# MRCS-ODX4_v17.net
KiCad netlist of a schematic drawn in EAGLE
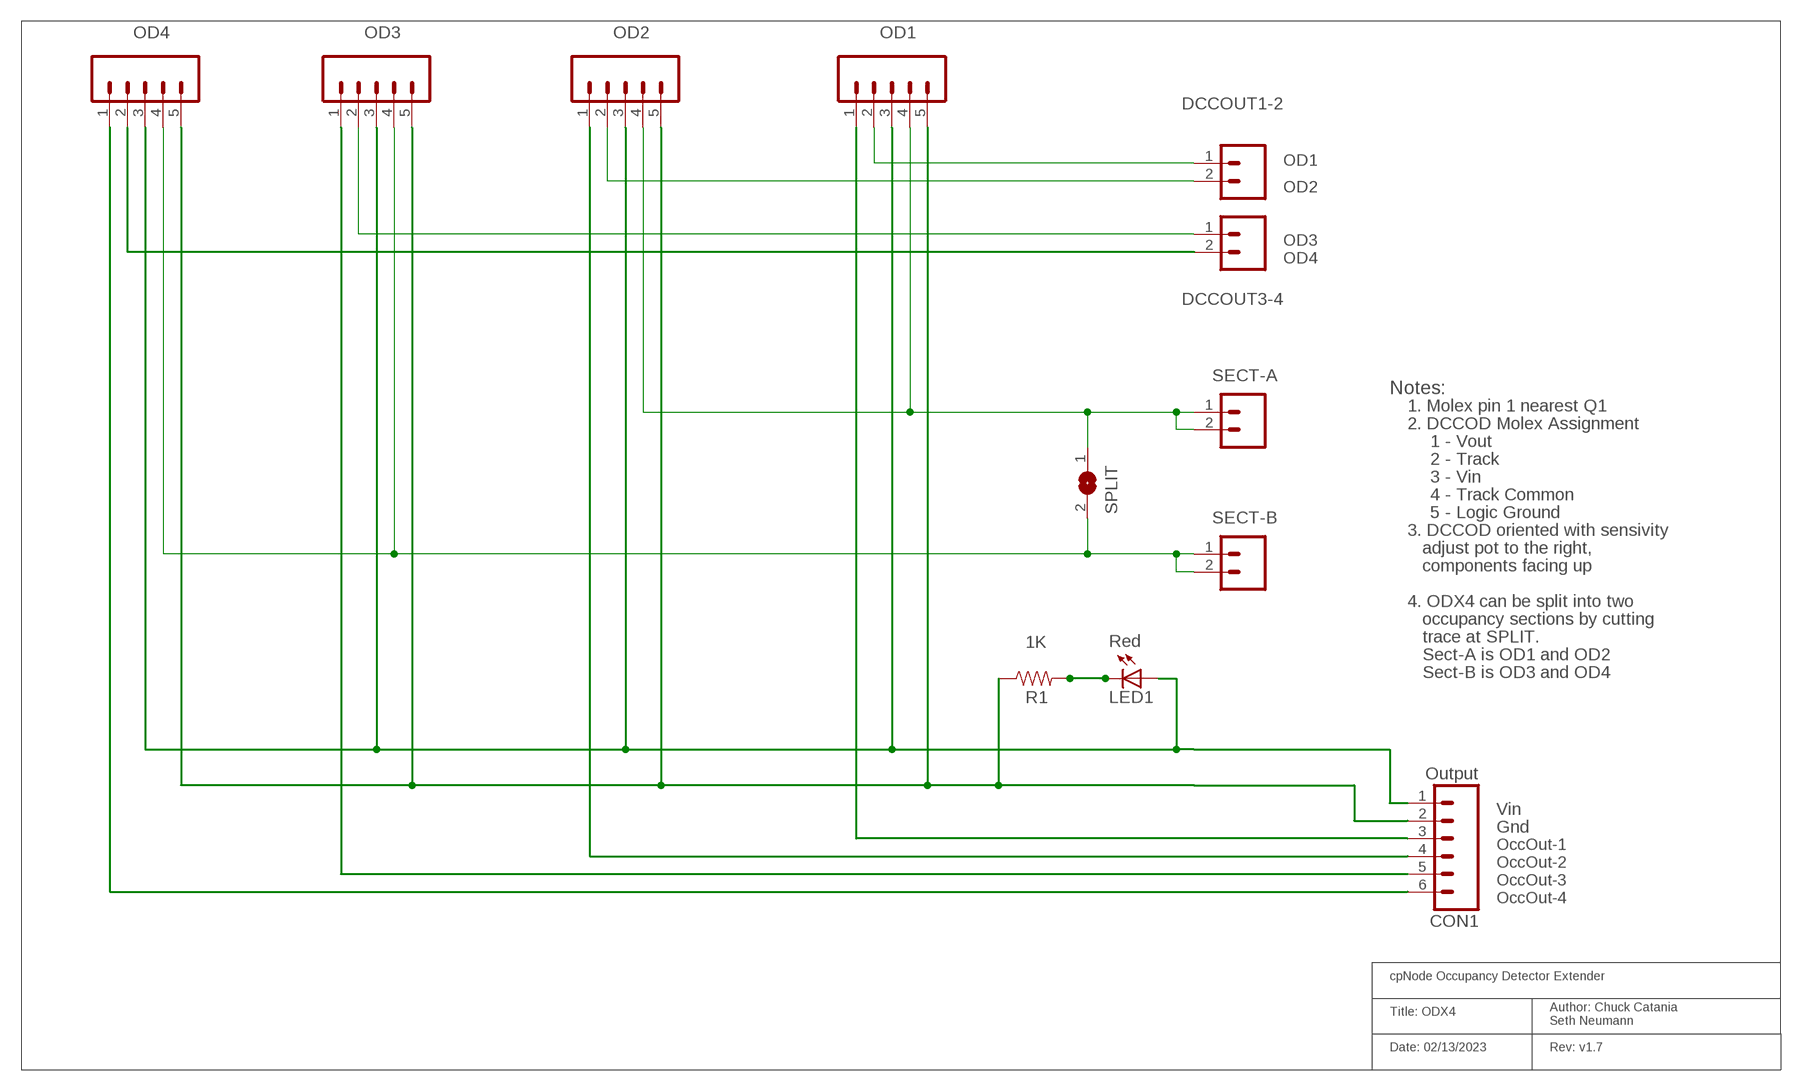
[diagram p0: schematic, sheet 1]

(export (version "E")
  (design (tool "Eeschema 10.0.6"))
  (components
    (comp (ref "CON1")
      (value "Output")
      (footprint "eagle-import:MOLEX-1X6_LOCK")
      (libsource (lib "eagle-import") (part "CONNECTOR-M06POLAR_LOCK"))
    )
    (comp (ref "DCCOUT1-2")
      (value "CONNECTOR-M025MM-LOCK")
      (footprint "eagle-import:SCREWTERMINAL-5MM-2")
      (libsource (lib "eagle-import") (part "CONNECTOR-M025MM-LOCK"))
    )
    (comp (ref "DCCOUT3-4")
      (value "CONNECTOR-M025MM-LOCK")
      (footprint "eagle-import:SCREWTERMINAL-5MM-2")
      (libsource (lib "eagle-import") (part "CONNECTOR-M025MM-LOCK"))
    )
    (comp (ref "LED1")
      (value "Red")
      (footprint "eagle-import:LED3MM")
      (libsource (lib "eagle-import") (part "LEDLED3MM"))
    )
    (comp (ref "OD1")
      (value "M05PTH_LONGPADS")
      (footprint "eagle-import:1X05_LONGPADS")
      (libsource (lib "eagle-import") (part "M05PTH_LONGPADS"))
    )
    (comp (ref "OD2")
      (value "M05PTH_LONGPADS")
      (footprint "eagle-import:1X05_LONGPADS")
      (libsource (lib "eagle-import") (part "M05PTH_LONGPADS"))
    )
    (comp (ref "OD3")
      (value "M05PTH_LONGPADS")
      (footprint "eagle-import:1X05_LONGPADS")
      (libsource (lib "eagle-import") (part "M05PTH_LONGPADS"))
    )
    (comp (ref "OD4")
      (value "M05PTH_LONGPADS")
      (footprint "eagle-import:1X05_LONGPADS")
      (libsource (lib "eagle-import") (part "M05PTH_LONGPADS"))
    )
    (comp (ref "R1")
      (value "1K")
      (footprint "eagle-import:AXIAL-0.4-RES")
      (libsource (lib "eagle-import") (part "RPTH04"))
    )
    (comp (ref "SECT-A")
      (value "M025MM")
      (footprint "eagle-import:SCREWTERMINAL-5MM-2")
      (libsource (lib "eagle-import") (part "M025MM"))
    )
    (comp (ref "SECT-B")
      (value "M025MM")
      (footprint "eagle-import:SCREWTERMINAL-5MM-2")
      (libsource (lib "eagle-import") (part "M025MM"))
    )
    (comp (ref "SPLIT")
      (value "SJW")
      (footprint "eagle-import:SJW")
      (libsource (lib "eagle-import") (part "SJW"))
    )
  )
  (nets
    (net (code "1") (name "Net-(CON1-Pad1)") (class "Default")
      (node (ref "CON1") (pin "1") (pinfunction "1_1") (pintype "passive"))
      (node (ref "LED1") (pin "A") (pinfunction "A_A") (pintype "passive"))
      (node (ref "OD1") (pin "3") (pinfunction "3_3") (pintype "passive"))
      (node (ref "OD2") (pin "3") (pinfunction "3_3") (pintype "passive"))
      (node (ref "OD3") (pin "3") (pinfunction "3_3") (pintype "passive"))
      (node (ref "OD4") (pin "3") (pinfunction "3_3") (pintype "passive"))
    )
    (net (code "2") (name "Net-(CON1-Pad3)") (class "Default")
      (node (ref "CON1") (pin "3") (pinfunction "3_3") (pintype "passive"))
      (node (ref "OD1") (pin "1") (pinfunction "1_1") (pintype "passive"))
    )
    (net (code "3") (name "Net-(CON1-Pad4)") (class "Default")
      (node (ref "CON1") (pin "4") (pinfunction "4_4") (pintype "passive"))
      (node (ref "OD2") (pin "1") (pinfunction "1_1") (pintype "passive"))
    )
    (net (code "4") (name "Net-(CON1-Pad5)") (class "Default")
      (node (ref "CON1") (pin "5") (pinfunction "5_5") (pintype "passive"))
      (node (ref "OD3") (pin "1") (pinfunction "1_1") (pintype "passive"))
    )
    (net (code "5") (name "Net-(CON1-Pad6)") (class "Default")
      (node (ref "CON1") (pin "6") (pinfunction "6_6") (pintype "passive"))
      (node (ref "OD4") (pin "1") (pinfunction "1_1") (pintype "passive"))
    )
    (net (code "6") (name "Net-(DCCOUT1-2-A)") (class "Default")
      (node (ref "DCCOUT1-2") (pin "1") (pinfunction "A_1") (pintype "passive"))
      (node (ref "OD1") (pin "2") (pinfunction "2_2") (pintype "passive"))
    )
    (net (code "7") (name "Net-(DCCOUT1-2-B)") (class "Default")
      (node (ref "DCCOUT1-2") (pin "2") (pinfunction "B_2") (pintype "passive"))
      (node (ref "OD2") (pin "2") (pinfunction "2_2") (pintype "passive"))
    )
    (net (code "8") (name "Net-(DCCOUT3-4-A)") (class "Default")
      (node (ref "DCCOUT3-4") (pin "1") (pinfunction "A_1") (pintype "passive"))
      (node (ref "OD3") (pin "2") (pinfunction "2_2") (pintype "passive"))
    )
    (net (code "9") (name "Net-(DCCOUT3-4-B)") (class "Default")
      (node (ref "DCCOUT3-4") (pin "2") (pinfunction "B_2") (pintype "passive"))
      (node (ref "OD4") (pin "2") (pinfunction "2_2") (pintype "passive"))
    )
    (net (code "10") (name "Net-(LED1-C)") (class "Default")
      (node (ref "LED1") (pin "K") (pinfunction "C_K") (pintype "passive"))
      (node (ref "R1") (pin "P$2") (pinfunction "2_P$2") (pintype "passive"))
    )
    (net (code "11") (name "Net-(OD1-Pad4)") (class "Default")
      (node (ref "OD1") (pin "4") (pinfunction "4_4") (pintype "passive"))
      (node (ref "OD2") (pin "4") (pinfunction "4_4") (pintype "passive"))
      (node (ref "SECT-A") (pin "1") (pinfunction "1_1") (pintype "passive"))
      (node (ref "SECT-A") (pin "2") (pinfunction "2_2") (pintype "passive"))
      (node (ref "SPLIT") (pin "1") (pinfunction "1_1") (pintype "passive"))
    )
    (net (code "12") (name "Net-(OD3-Pad4)") (class "Default")
      (node (ref "OD3") (pin "4") (pinfunction "4_4") (pintype "passive"))
      (node (ref "OD4") (pin "4") (pinfunction "4_4") (pintype "passive"))
      (node (ref "SECT-B") (pin "1") (pinfunction "1_1") (pintype "passive"))
      (node (ref "SECT-B") (pin "2") (pinfunction "2_2") (pintype "passive"))
      (node (ref "SPLIT") (pin "2") (pinfunction "2_2") (pintype "passive"))
    )
    (net (code "13") (name "Net-(R1-1)") (class "Default")
      (node (ref "CON1") (pin "2") (pinfunction "2_2") (pintype "passive"))
      (node (ref "OD1") (pin "5") (pinfunction "5_5") (pintype "passive"))
      (node (ref "OD2") (pin "5") (pinfunction "5_5") (pintype "passive"))
      (node (ref "OD3") (pin "5") (pinfunction "5_5") (pintype "passive"))
      (node (ref "OD4") (pin "5") (pinfunction "5_5") (pintype "passive"))
      (node (ref "R1") (pin "P$1") (pinfunction "1_P$1") (pintype "passive"))
    )
  )
)
